# rx_mod.net
KiCad netlist of a schematic drawn in EAGLE
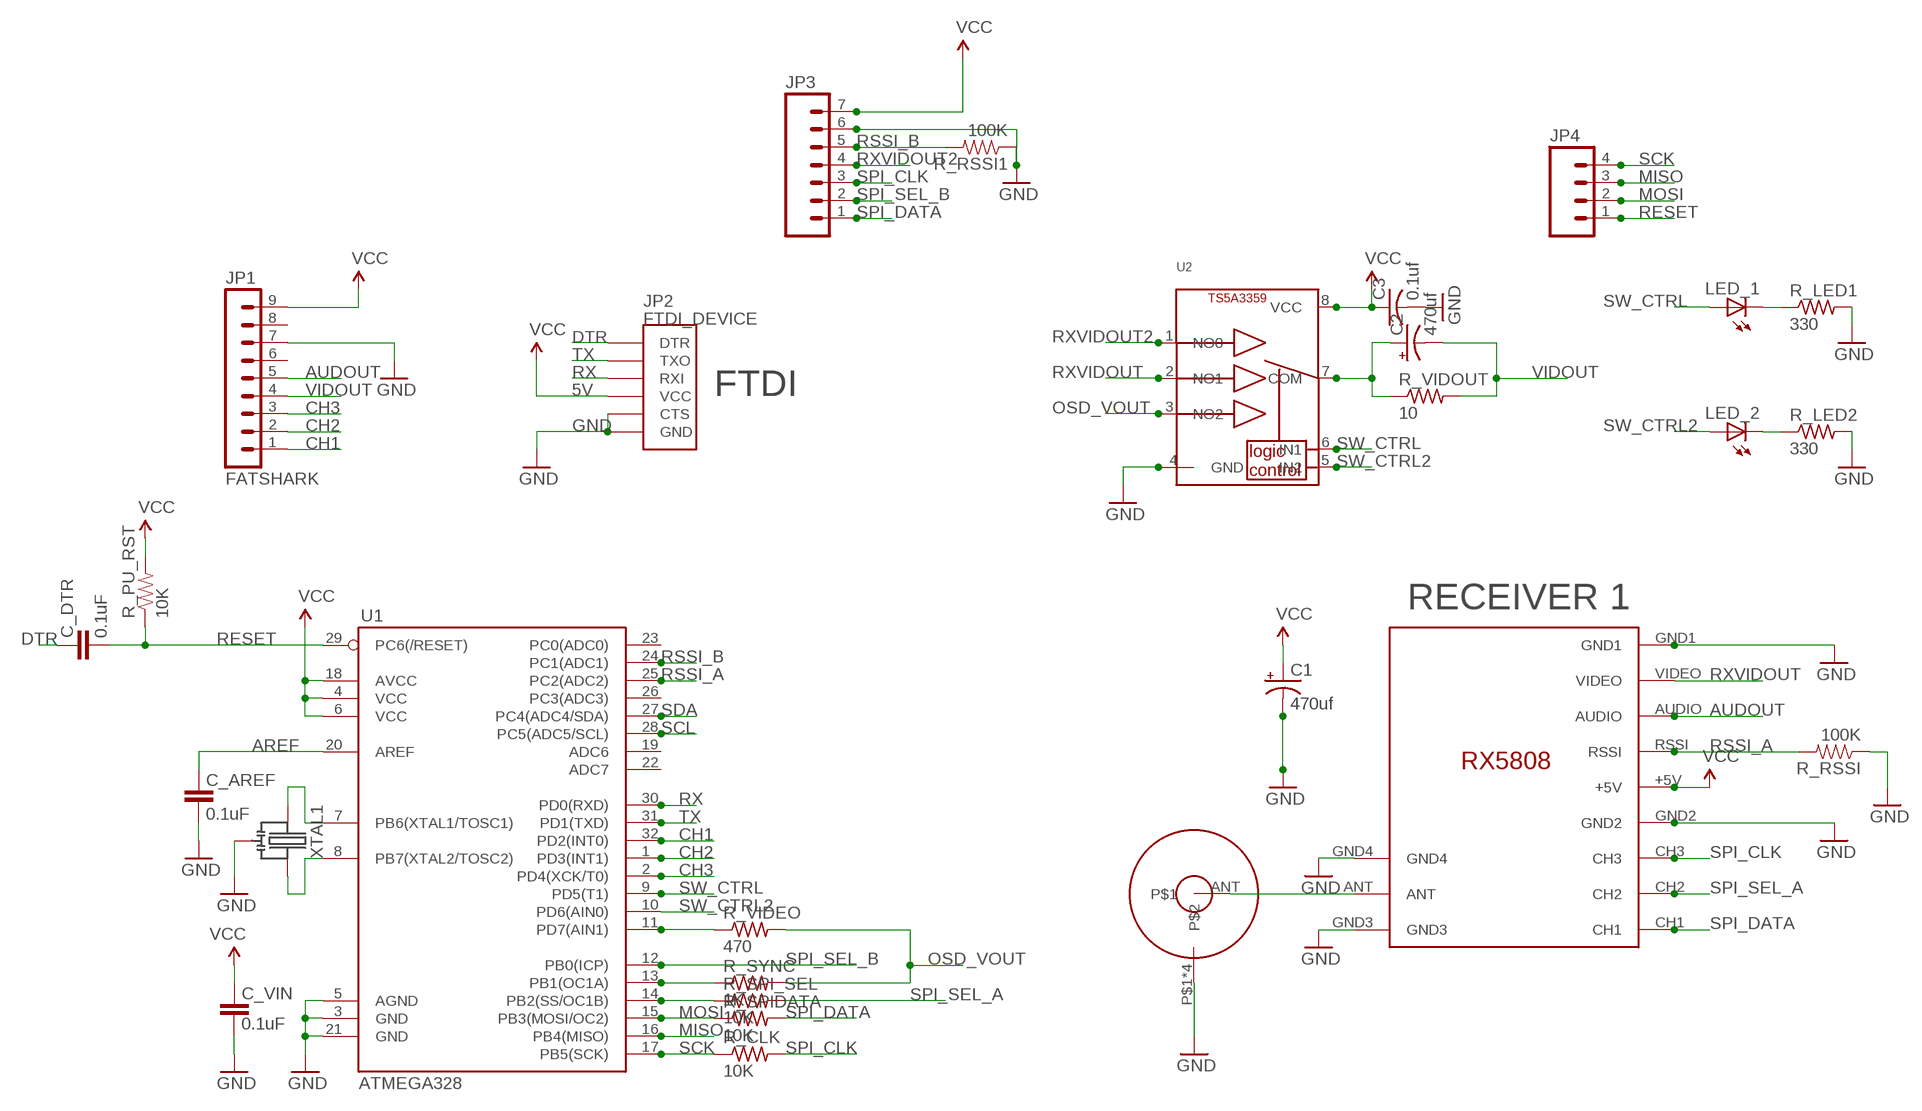
[diagram p0: schematic, sheet 1]

(export (version "E")
  (design (tool "Eeschema 10.0.6"))
  (components
    (comp (ref "C1")
      (value "470uf")
      (footprint "eagle-import:EIA7343")
      (libsource (lib "eagle-import") (part "CAP_POL7343"))
    )
    (comp (ref "C2")
      (value "470uf")
      (footprint "eagle-import:EIA7343")
      (libsource (lib "eagle-import") (part "CAP_POL7343"))
    )
    (comp (ref "C3")
      (value "0.1uf")
      (footprint "eagle-import:C0603")
      (libsource (lib "eagle-import") (part "C-USC0603"))
    )
    (comp (ref "C_AREF")
      (value "0.1uF")
      (footprint "eagle-import:0603-CAP")
      (libsource (lib "eagle-import") (part "CAP0603-CAP"))
    )
    (comp (ref "C_DTR")
      (value "0.1uF")
      (footprint "eagle-import:0603-CAP")
      (libsource (lib "eagle-import") (part "CAP0603-CAP"))
    )
    (comp (ref "C_VIN")
      (value "0.1uF")
      (footprint "eagle-import:0603-CAP")
      (libsource (lib "eagle-import") (part "CAP0603-CAP"))
    )
    (comp (ref "JP1")
      (value "FATSHARK")
      (footprint "eagle-import:MA09-1")
      (libsource (lib "eagle-import") (part "MA09-1"))
    )
    (comp (ref "JP2")
      (value "FTDI_DEVICE")
      (footprint "eagle-import:FTDI_DEVICE_SIDE")
      (libsource (lib "eagle-import") (part "FTDI_DEVICE"))
    )
    (comp (ref "JP3")
      (value "M07")
      (footprint "eagle-import:1X07")
      (libsource (lib "eagle-import") (part "M07"))
    )
    (comp (ref "JP4")
      (value "M04PTH")
      (footprint "eagle-import:1X04")
      (libsource (lib "eagle-import") (part "M04PTH"))
    )
    (comp (ref "LED_1")
      (value "LEDSML0603")
      (footprint "eagle-import:SML0603")
      (libsource (lib "eagle-import") (part "LEDSML0603"))
    )
    (comp (ref "LED_2")
      (value "LEDSML0603")
      (footprint "eagle-import:SML0603")
      (libsource (lib "eagle-import") (part "LEDSML0603"))
    )
    (comp (ref "RECEIVER_A")
      (value "RX5808_A")
      (footprint "eagle-import:RX5808")
      (libsource (lib "eagle-import") (part "RX5808"))
    )
    (comp (ref "R_CLK")
      (value "10K")
      (footprint "eagle-import:R0805")
      (libsource (lib "eagle-import") (part "R-US_R0805"))
    )
    (comp (ref "R_LED1")
      (value "330")
      (footprint "eagle-import:R0603")
      (libsource (lib "eagle-import") (part "R-US_R0603"))
    )
    (comp (ref "R_LED2")
      (value "330")
      (footprint "eagle-import:R0603")
      (libsource (lib "eagle-import") (part "R-US_R0603"))
    )
    (comp (ref "R_PU_RST")
      (value "10K")
      (footprint "eagle-import:0603-RES")
      (libsource (lib "eagle-import") (part "RESISTOR0603-RES"))
    )
    (comp (ref "R_RSSI")
      (value "100K")
      (footprint "eagle-import:0603-RES")
      (libsource (lib "eagle-import") (part "RESISTOR0603-RES"))
    )
    (comp (ref "R_RSSI1")
      (value "100K")
      (footprint "eagle-import:0603-RES")
      (libsource (lib "eagle-import") (part "RESISTOR0603-RES"))
    )
    (comp (ref "R_SPIDATA")
      (value "10K")
      (footprint "eagle-import:R0805")
      (libsource (lib "eagle-import") (part "R-US_R0805"))
    )
    (comp (ref "R_SPI_SEL")
      (value "10K")
      (footprint "eagle-import:R0805")
      (libsource (lib "eagle-import") (part "R-US_R0805"))
    )
    (comp (ref "R_SYNC")
      (value "1K")
      (footprint "eagle-import:R0805")
      (libsource (lib "eagle-import") (part "R-US_R0805"))
    )
    (comp (ref "R_VIDEO")
      (value "470")
      (footprint "eagle-import:R0805")
      (libsource (lib "eagle-import") (part "R-US_R0805"))
    )
    (comp (ref "R_VIDOUT")
      (value "10")
      (footprint "eagle-import:R0805")
      (libsource (lib "eagle-import") (part "R-US_R0805"))
    )
    (comp (ref "U$1")
      (value "SMA_ANTENNA")
      (footprint "eagle-import:SMA_CONNECTOR")
      (libsource (lib "eagle-import") (part "SMA_ANTENNA"))
    )
    (comp (ref "U1")
      (value "ATMEGA328")
      (footprint "eagle-import:TQFP32-08")
      (libsource (lib "eagle-import") (part "ATMEGA168"))
    )
    (comp (ref "U2")
      (value "TS5A3359")
      (footprint "eagle-import:VFSOP-8")
      (libsource (lib "eagle-import") (part "TS5A3359"))
    )
    (comp (ref "XTAL1")
      (value "CSTCE16M0V53-R0")
      (footprint "eagle-import:CSTCE16M0V53-R0")
      (libsource (lib "eagle-import") (part "CSTCE16M0V53-R0"))
    )
  )
  (nets
    (net (code "1") (name "/AREF") (class "Default")
      (node (ref "C_AREF") (pin "2") (pinfunction "2_2") (pintype "passive"))
      (node (ref "U1") (pin "20") (pinfunction "AREF_20") (pintype "bidirectional"))
    )
    (net (code "2") (name "/AUDOUT") (class "Default")
      (node (ref "JP1") (pin "5") (pinfunction "5_5") (pintype "passive"))
      (node (ref "RECEIVER_A") (pin "AUDIO") (pinfunction "AUDIO_AUDIO") (pintype "bidirectional"))
    )
    (net (code "3") (name "/CH1") (class "Default")
      (node (ref "JP1") (pin "1") (pinfunction "1_1") (pintype "passive"))
      (node (ref "U1") (pin "32") (pinfunction "PD2(INT0)_32") (pintype "bidirectional"))
    )
    (net (code "4") (name "/CH2") (class "Default")
      (node (ref "JP1") (pin "2") (pinfunction "2_2") (pintype "passive"))
      (node (ref "U1") (pin "1") (pinfunction "PD3(INT1)_1") (pintype "bidirectional"))
    )
    (net (code "5") (name "/CH3") (class "Default")
      (node (ref "JP1") (pin "3") (pinfunction "3_3") (pintype "passive"))
      (node (ref "U1") (pin "2") (pinfunction "PD4(XCK/T0)_2") (pintype "bidirectional"))
    )
    (net (code "6") (name "/DTR") (class "Default")
      (node (ref "C_DTR") (pin "2") (pinfunction "2_2") (pintype "passive"))
      (node (ref "JP2") (pin "P$1") (pinfunction "DTR_P$1") (pintype "bidirectional"))
    )
    (net (code "7") (name "/MISO") (class "Default")
      (node (ref "JP4") (pin "3") (pinfunction "3_3") (pintype "passive"))
      (node (ref "U1") (pin "16") (pinfunction "PB4(MISO)_16") (pintype "bidirectional"))
    )
    (net (code "8") (name "/MOSI") (class "Default")
      (node (ref "JP4") (pin "2") (pinfunction "2_2") (pintype "passive"))
      (node (ref "R_SPIDATA") (pin "1") (pinfunction "1_1") (pintype "passive"))
      (node (ref "U1") (pin "15") (pinfunction "PB3(MOSI/OC2)_15") (pintype "bidirectional"))
    )
    (net (code "9") (name "/OSD_VOUT") (class "Default")
      (node (ref "R_SYNC") (pin "2") (pinfunction "2_2") (pintype "passive"))
      (node (ref "R_VIDEO") (pin "2") (pinfunction "2_2") (pintype "passive"))
      (node (ref "U2") (pin "3") (pinfunction "NO2_3") (pintype "input"))
    )
    (net (code "10") (name "/RESET") (class "Default")
      (node (ref "C_DTR") (pin "1") (pinfunction "1_1") (pintype "passive"))
      (node (ref "JP4") (pin "1") (pinfunction "1_1") (pintype "passive"))
      (node (ref "R_PU_RST") (pin "1") (pinfunction "1_1") (pintype "passive"))
      (node (ref "U1") (pin "29") (pinfunction "PC6(/RESET)_29") (pintype "bidirectional"))
    )
    (net (code "11") (name "/RSSI_A") (class "Default")
      (node (ref "RECEIVER_A") (pin "RSSI") (pinfunction "RSSI_RSSI") (pintype "bidirectional"))
      (node (ref "R_RSSI") (pin "2") (pinfunction "2_2") (pintype "passive"))
      (node (ref "U1") (pin "25") (pinfunction "PC2(ADC2)_25") (pintype "bidirectional"))
    )
    (net (code "12") (name "/RSSI_B") (class "Default")
      (node (ref "JP3") (pin "5") (pinfunction "5_5") (pintype "passive"))
      (node (ref "R_RSSI1") (pin "2") (pinfunction "2_2") (pintype "passive"))
      (node (ref "U1") (pin "24") (pinfunction "PC1(ADC1)_24") (pintype "bidirectional"))
    )
    (net (code "13") (name "/RX") (class "Default")
      (node (ref "JP2") (pin "P$3") (pinfunction "RXI_P$3") (pintype "bidirectional"))
      (node (ref "U1") (pin "30") (pinfunction "PD0(RXD)_30") (pintype "bidirectional"))
    )
    (net (code "14") (name "/RXVIDOUT") (class "Default")
      (node (ref "RECEIVER_A") (pin "VIDEO") (pinfunction "VIDEO_VIDEO") (pintype "bidirectional"))
      (node (ref "U2") (pin "2") (pinfunction "NO1_2") (pintype "input"))
    )
    (net (code "15") (name "/RXVIDOUT2") (class "Default")
      (node (ref "JP3") (pin "4") (pinfunction "4_4") (pintype "passive"))
      (node (ref "U2") (pin "1") (pinfunction "NO0_1") (pintype "input"))
    )
    (net (code "16") (name "/SCK") (class "Default")
      (node (ref "JP4") (pin "4") (pinfunction "4_4") (pintype "passive"))
      (node (ref "R_CLK") (pin "1") (pinfunction "1_1") (pintype "passive"))
      (node (ref "U1") (pin "17") (pinfunction "PB5(SCK)_17") (pintype "bidirectional"))
    )
    (net (code "17") (name "/SCL") (class "Default")
      (node (ref "U1") (pin "28") (pinfunction "PC5(ADC5/SCL)_28") (pintype "bidirectional"))
    )
    (net (code "18") (name "/SDA") (class "Default")
      (node (ref "U1") (pin "27") (pinfunction "PC4(ADC4/SDA)_27") (pintype "bidirectional"))
    )
    (net (code "19") (name "/SPI_CLK") (class "Default")
      (node (ref "JP3") (pin "3") (pinfunction "3_3") (pintype "passive"))
      (node (ref "RECEIVER_A") (pin "CH3") (pinfunction "CH3_CH3") (pintype "bidirectional"))
      (node (ref "R_CLK") (pin "2") (pinfunction "2_2") (pintype "passive"))
    )
    (net (code "20") (name "/SPI_DATA") (class "Default")
      (node (ref "JP3") (pin "1") (pinfunction "1_1") (pintype "passive"))
      (node (ref "RECEIVER_A") (pin "CH1") (pinfunction "CH1_CH1") (pintype "bidirectional"))
      (node (ref "R_SPIDATA") (pin "2") (pinfunction "2_2") (pintype "passive"))
    )
    (net (code "21") (name "/SPI_SEL_A") (class "Default")
      (node (ref "RECEIVER_A") (pin "CH2") (pinfunction "CH2_CH2") (pintype "bidirectional"))
      (node (ref "R_SPI_SEL") (pin "2") (pinfunction "2_2") (pintype "passive"))
    )
    (net (code "22") (name "/SPI_SEL_B") (class "Default")
      (node (ref "JP3") (pin "2") (pinfunction "2_2") (pintype "passive"))
      (node (ref "U1") (pin "12") (pinfunction "PB0(ICP)_12") (pintype "bidirectional"))
    )
    (net (code "23") (name "/SW_CTRL") (class "Default")
      (node (ref "LED_1") (pin "A") (pinfunction "A_A") (pintype "passive"))
      (node (ref "U1") (pin "9") (pinfunction "PD5(T1)_9") (pintype "bidirectional"))
      (node (ref "U2") (pin "6") (pinfunction "IN1_6") (pintype "output"))
    )
    (net (code "24") (name "/SW_CTRL2") (class "Default")
      (node (ref "LED_2") (pin "A") (pinfunction "A_A") (pintype "passive"))
      (node (ref "U1") (pin "10") (pinfunction "PD6(AIN0)_10") (pintype "bidirectional"))
      (node (ref "U2") (pin "5") (pinfunction "IN2_5") (pintype "output"))
    )
    (net (code "25") (name "/TX") (class "Default")
      (node (ref "JP2") (pin "P$2") (pinfunction "TXO_P$2") (pintype "bidirectional"))
      (node (ref "U1") (pin "31") (pinfunction "PD1(TXD)_31") (pintype "bidirectional"))
    )
    (net (code "26") (name "/VIDOUT") (class "Default")
      (node (ref "C2") (pin "C") (pinfunction "-_C") (pintype "passive"))
      (node (ref "JP1") (pin "4") (pinfunction "4_4") (pintype "passive"))
      (node (ref "R_VIDOUT") (pin "2") (pinfunction "2_2") (pintype "passive"))
    )
    (net (code "27") (name "GND") (class "Default")
      (node (ref "C1") (pin "C") (pinfunction "-_C") (pintype "passive"))
      (node (ref "C3") (pin "2") (pinfunction "2_2") (pintype "passive"))
      (node (ref "C_AREF") (pin "1") (pinfunction "1_1") (pintype "passive"))
      (node (ref "C_VIN") (pin "1") (pinfunction "1_1") (pintype "passive"))
      (node (ref "JP1") (pin "7") (pinfunction "7_7") (pintype "passive"))
      (node (ref "JP2") (pin "P$5") (pinfunction "CTS_P$5") (pintype "bidirectional"))
      (node (ref "JP2") (pin "P$6") (pinfunction "GND_P$6") (pintype "bidirectional"))
      (node (ref "JP3") (pin "6") (pinfunction "6_6") (pintype "passive"))
      (node (ref "RECEIVER_A") (pin "GND1") (pinfunction "GND1_GND1") (pintype "bidirectional"))
      (node (ref "RECEIVER_A") (pin "GND2") (pinfunction "GND2_GND2") (pintype "bidirectional"))
      (node (ref "RECEIVER_A") (pin "GND3") (pinfunction "GND3_GND3") (pintype "bidirectional"))
      (node (ref "RECEIVER_A") (pin "GND4") (pinfunction "GND4_GND4") (pintype "bidirectional"))
      (node (ref "R_LED1") (pin "2") (pinfunction "2_2") (pintype "passive"))
      (node (ref "R_LED2") (pin "2") (pinfunction "2_2") (pintype "passive"))
      (node (ref "R_RSSI") (pin "1") (pinfunction "1_1") (pintype "passive"))
      (node (ref "R_RSSI1") (pin "1") (pinfunction "1_1") (pintype "passive"))
      (node (ref "U$1") (pin "P$1") (pinfunction "P$2_P$1") (pintype "bidirectional"))
      (node (ref "U$1") (pin "P$2") (pinfunction "P$2_P$2") (pintype "bidirectional"))
      (node (ref "U$1") (pin "P$3") (pinfunction "P$2_P$3") (pintype "bidirectional"))
      (node (ref "U$1") (pin "P$4") (pinfunction "P$2_P$4") (pintype "bidirectional"))
      (node (ref "U1") (pin "21") (pinfunction "GND_21") (pintype "bidirectional"))
      (node (ref "U1") (pin "3") (pinfunction "GND_3") (pintype "bidirectional"))
      (node (ref "U1") (pin "5") (pinfunction "AGND_5") (pintype "bidirectional"))
      (node (ref "U2") (pin "4") (pinfunction "GND_4") (pintype "power_in"))
      (node (ref "XTAL1") (pin "2") (pinfunction "2_2") (pintype "bidirectional"))
    )
    (net (code "28") (name "Net-(C2-+)") (class "Default")
      (node (ref "C2") (pin "A") (pinfunction "+_A") (pintype "passive"))
      (node (ref "R_VIDOUT") (pin "1") (pinfunction "1_1") (pintype "passive"))
      (node (ref "U2") (pin "7") (pinfunction "COM_7") (pintype "input"))
    )
    (net (code "29") (name "Net-(LED_1-PadC)") (class "Default")
      (node (ref "LED_1") (pin "C") (pinfunction "C_C") (pintype "passive"))
      (node (ref "R_LED1") (pin "1") (pinfunction "1_1") (pintype "passive"))
    )
    (net (code "30") (name "Net-(LED_2-PadC)") (class "Default")
      (node (ref "LED_2") (pin "C") (pinfunction "C_C") (pintype "passive"))
      (node (ref "R_LED2") (pin "1") (pinfunction "1_1") (pintype "passive"))
    )
    (net (code "31") (name "Net-(U$1-P$1)") (class "Default")
      (node (ref "RECEIVER_A") (pin "ANT") (pinfunction "ANT_ANT") (pintype "bidirectional"))
      (node (ref "U$1") (pin "ANT") (pinfunction "P$1_ANT") (pintype "bidirectional"))
    )
    (net (code "32") (name "Net-(U1-PB1(OC1A))") (class "Default")
      (node (ref "R_SYNC") (pin "1") (pinfunction "1_1") (pintype "passive"))
      (node (ref "U1") (pin "13") (pinfunction "PB1(OC1A)_13") (pintype "bidirectional"))
    )
    (net (code "33") (name "Net-(U1-PB2(SS{slash}OC1B))") (class "Default")
      (node (ref "R_SPI_SEL") (pin "1") (pinfunction "1_1") (pintype "passive"))
      (node (ref "U1") (pin "14") (pinfunction "PB2(SS/OC1B)_14") (pintype "bidirectional"))
    )
    (net (code "34") (name "Net-(U1-PB6(XTAL1{slash}TOSC1))") (class "Default")
      (node (ref "U1") (pin "7") (pinfunction "PB6(XTAL1/TOSC1)_7") (pintype "bidirectional"))
      (node (ref "XTAL1") (pin "1") (pinfunction "1_1") (pintype "bidirectional"))
    )
    (net (code "35") (name "Net-(U1-PB7(XTAL2{slash}TOSC2))") (class "Default")
      (node (ref "U1") (pin "8") (pinfunction "PB7(XTAL2/TOSC2)_8") (pintype "bidirectional"))
      (node (ref "XTAL1") (pin "3") (pinfunction "3_3") (pintype "bidirectional"))
    )
    (net (code "36") (name "Net-(U1-PD7(AIN1))") (class "Default")
      (node (ref "R_VIDEO") (pin "1") (pinfunction "1_1") (pintype "passive"))
      (node (ref "U1") (pin "11") (pinfunction "PD7(AIN1)_11") (pintype "bidirectional"))
    )
    (net (code "37") (name "VCC") (class "Default")
      (node (ref "C1") (pin "A") (pinfunction "+_A") (pintype "passive"))
      (node (ref "C3") (pin "1") (pinfunction "1_1") (pintype "passive"))
      (node (ref "C_VIN") (pin "2") (pinfunction "2_2") (pintype "passive"))
      (node (ref "JP1") (pin "9") (pinfunction "9_9") (pintype "passive"))
      (node (ref "JP2") (pin "P$4") (pinfunction "VCC_P$4") (pintype "bidirectional"))
      (node (ref "JP3") (pin "7") (pinfunction "7_7") (pintype "passive"))
      (node (ref "RECEIVER_A") (pin "+5V") (pinfunction "+5V_+5V") (pintype "bidirectional"))
      (node (ref "R_PU_RST") (pin "2") (pinfunction "2_2") (pintype "passive"))
      (node (ref "U1") (pin "18") (pinfunction "AVCC_18") (pintype "bidirectional"))
      (node (ref "U1") (pin "4") (pinfunction "VCC_4") (pintype "bidirectional"))
      (node (ref "U1") (pin "6") (pinfunction "VCC_6") (pintype "bidirectional"))
      (node (ref "U2") (pin "8") (pinfunction "VCC_8") (pintype "power_in"))
    )
    (net (code "38") (name "unconnected-(JP1-Pad6)") (class "Default")
      (node (ref "JP1") (pin "6") (pinfunction "6_6") (pintype "passive"))
    )
    (net (code "39") (name "unconnected-(JP1-Pad8)") (class "Default")
      (node (ref "JP1") (pin "8") (pinfunction "8_8") (pintype "passive"))
    )
    (net (code "40") (name "unconnected-(U1-ADC6-Pad19)") (class "Default")
      (node (ref "U1") (pin "19") (pinfunction "ADC6_19") (pintype "bidirectional"))
    )
    (net (code "41") (name "unconnected-(U1-ADC7-Pad22)") (class "Default")
      (node (ref "U1") (pin "22") (pinfunction "ADC7_22") (pintype "bidirectional"))
    )
    (net (code "42") (name "unconnected-(U1-PC0(ADC0)-Pad23)") (class "Default")
      (node (ref "U1") (pin "23") (pinfunction "PC0(ADC0)_23") (pintype "bidirectional"))
    )
    (net (code "43") (name "unconnected-(U1-PC3(ADC3)-Pad26)") (class "Default")
      (node (ref "U1") (pin "26") (pinfunction "PC3(ADC3)_26") (pintype "bidirectional"))
    )
  )
)
